# Faceh.net
KiCad netlist of a schematic drawn in EAGLE
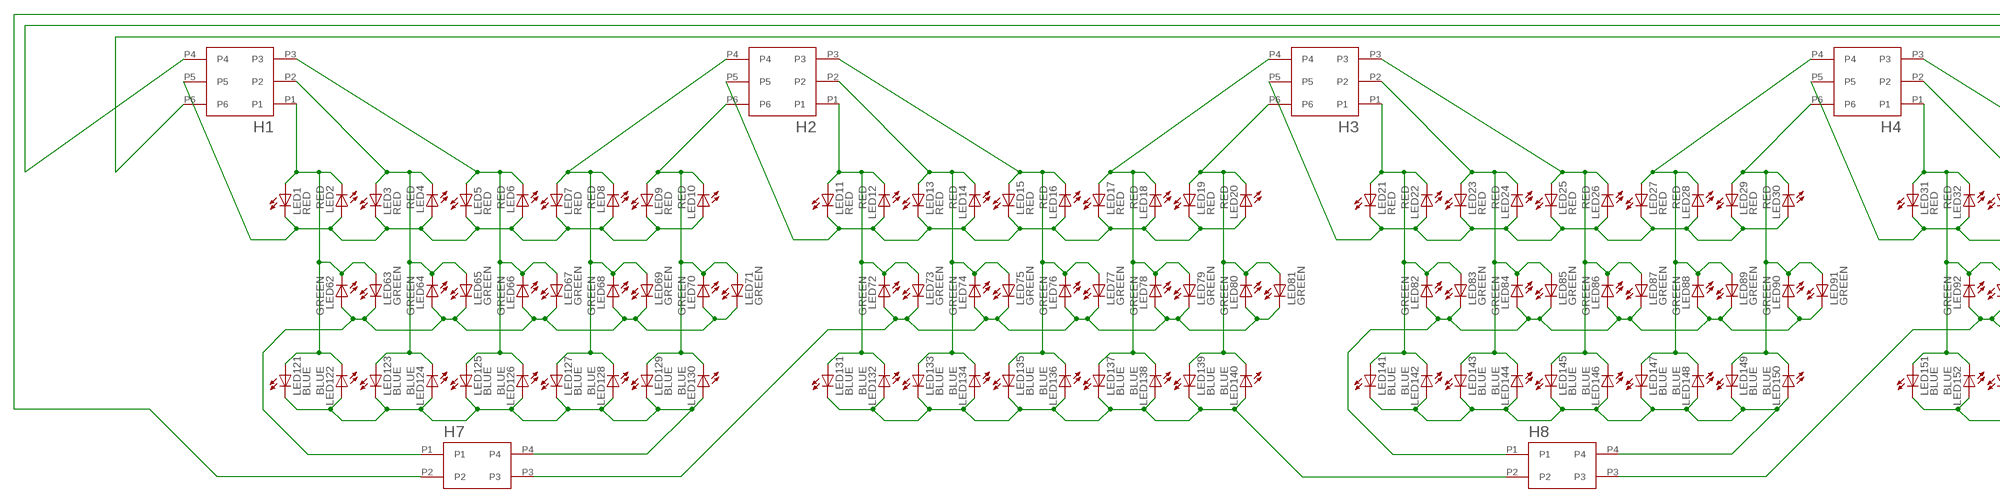
[diagram p0: schematic, sheet 1, part 1 of 2]
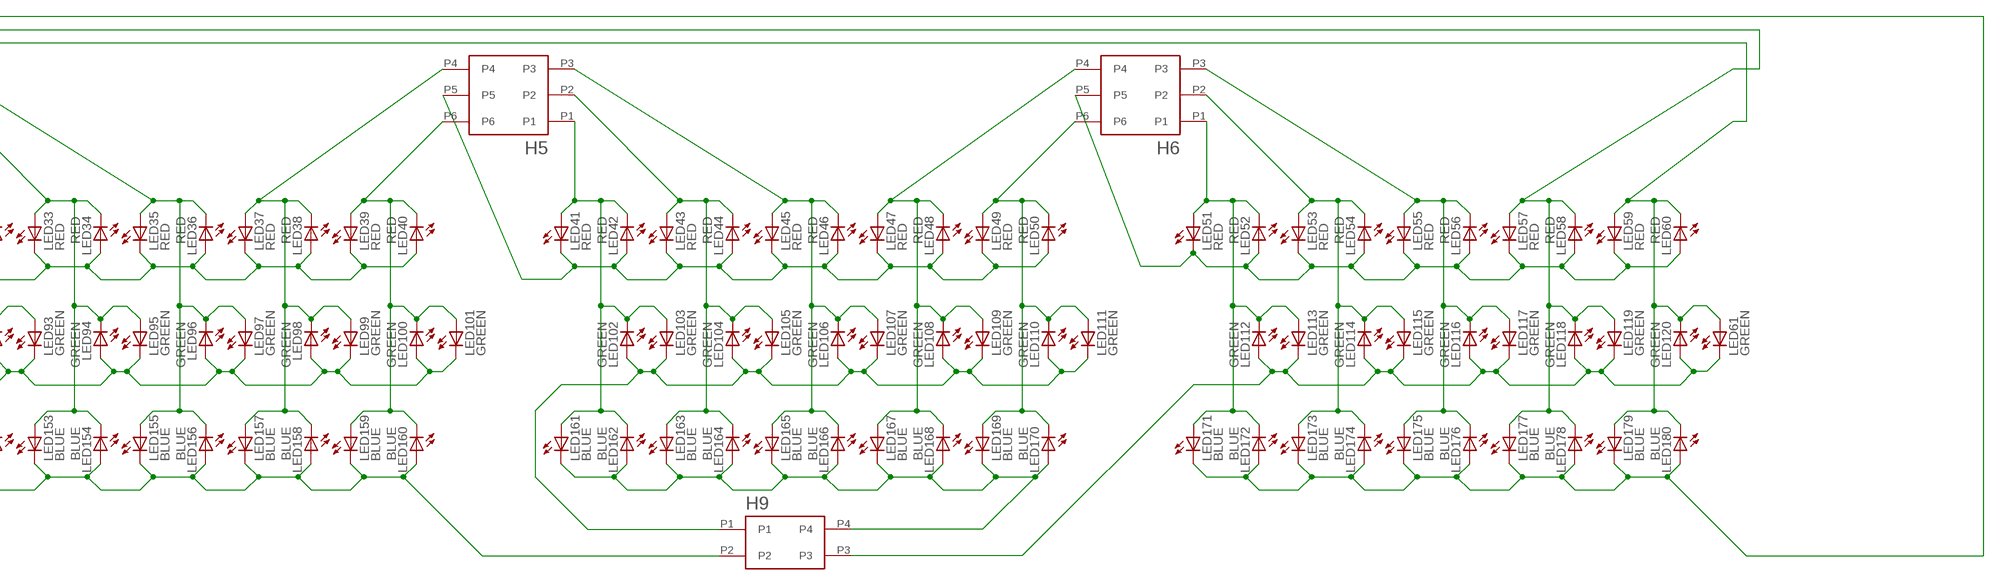
[diagram p1: schematic, sheet 1, part 2 of 2]

(export (version "E")
  (design (tool "Eeschema 10.0.6"))
  (components
    (comp (ref "H1")
      (value "2X3")
      (footprint "eagle-import:3X2_1MM_SMD")
      (libsource (lib "eagle-import") (part "2X3"))
    )
    (comp (ref "H2")
      (value "2X3")
      (footprint "eagle-import:3X2_1MM_SMD")
      (libsource (lib "eagle-import") (part "2X3"))
    )
    (comp (ref "H3")
      (value "2X3")
      (footprint "eagle-import:3X2_1MM_SMD")
      (libsource (lib "eagle-import") (part "2X3"))
    )
    (comp (ref "H4")
      (value "2X3")
      (footprint "eagle-import:3X2_1MM_SMD")
      (libsource (lib "eagle-import") (part "2X3"))
    )
    (comp (ref "H5")
      (value "2X3")
      (footprint "eagle-import:3X2_1MM_SMD")
      (libsource (lib "eagle-import") (part "2X3"))
    )
    (comp (ref "H6")
      (value "2X3")
      (footprint "eagle-import:3X2_1MM_SMD")
      (libsource (lib "eagle-import") (part "2X3"))
    )
    (comp (ref "H7")
      (value "2X2")
      (footprint "eagle-import:2X2_1MM_SMD")
      (libsource (lib "eagle-import") (part "2X2"))
    )
    (comp (ref "H8")
      (value "2X2")
      (footprint "eagle-import:2X2_1MM_SMD")
      (libsource (lib "eagle-import") (part "2X2"))
    )
    (comp (ref "H9")
      (value "2X2")
      (footprint "eagle-import:2X2_1MM_SMD")
      (libsource (lib "eagle-import") (part "2X2"))
    )
    (comp (ref "LED1")
      (value "RED")
      (footprint "eagle-import:LED-0603")
      (libsource (lib "eagle-import") (part "LED0603"))
    )
    (comp (ref "LED2")
      (value "RED")
      (footprint "eagle-import:LED-0603")
      (libsource (lib "eagle-import") (part "LED0603"))
    )
    (comp (ref "LED3")
      (value "RED")
      (footprint "eagle-import:LED-0603")
      (libsource (lib "eagle-import") (part "LED0603"))
    )
    (comp (ref "LED4")
      (value "RED")
      (footprint "eagle-import:LED-0603")
      (libsource (lib "eagle-import") (part "LED0603"))
    )
    (comp (ref "LED5")
      (value "RED")
      (footprint "eagle-import:LED-0603")
      (libsource (lib "eagle-import") (part "LED0603"))
    )
    (comp (ref "LED6")
      (value "RED")
      (footprint "eagle-import:LED-0603")
      (libsource (lib "eagle-import") (part "LED0603"))
    )
    (comp (ref "LED7")
      (value "RED")
      (footprint "eagle-import:LED-0603")
      (libsource (lib "eagle-import") (part "LED0603"))
    )
    (comp (ref "LED8")
      (value "RED")
      (footprint "eagle-import:LED-0603")
      (libsource (lib "eagle-import") (part "LED0603"))
    )
    (comp (ref "LED9")
      (value "RED")
      (footprint "eagle-import:LED-0603")
      (libsource (lib "eagle-import") (part "LED0603"))
    )
    (comp (ref "LED10")
      (value "RED")
      (footprint "eagle-import:LED-0603")
      (libsource (lib "eagle-import") (part "LED0603"))
    )
    (comp (ref "LED11")
      (value "RED")
      (footprint "eagle-import:LED-0603")
      (libsource (lib "eagle-import") (part "LED0603"))
    )
    (comp (ref "LED12")
      (value "RED")
      (footprint "eagle-import:LED-0603")
      (libsource (lib "eagle-import") (part "LED0603"))
    )
    (comp (ref "LED13")
      (value "RED")
      (footprint "eagle-import:LED-0603")
      (libsource (lib "eagle-import") (part "LED0603"))
    )
    (comp (ref "LED14")
      (value "RED")
      (footprint "eagle-import:LED-0603")
      (libsource (lib "eagle-import") (part "LED0603"))
    )
    (comp (ref "LED15")
      (value "RED")
      (footprint "eagle-import:LED-0603")
      (libsource (lib "eagle-import") (part "LED0603"))
    )
    (comp (ref "LED16")
      (value "RED")
      (footprint "eagle-import:LED-0603")
      (libsource (lib "eagle-import") (part "LED0603"))
    )
    (comp (ref "LED17")
      (value "RED")
      (footprint "eagle-import:LED-0603")
      (libsource (lib "eagle-import") (part "LED0603"))
    )
    (comp (ref "LED18")
      (value "RED")
      (footprint "eagle-import:LED-0603")
      (libsource (lib "eagle-import") (part "LED0603"))
    )
    (comp (ref "LED19")
      (value "RED")
      (footprint "eagle-import:LED-0603")
      (libsource (lib "eagle-import") (part "LED0603"))
    )
    (comp (ref "LED20")
      (value "RED")
      (footprint "eagle-import:LED-0603")
      (libsource (lib "eagle-import") (part "LED0603"))
    )
    (comp (ref "LED21")
      (value "RED")
      (footprint "eagle-import:LED-0603")
      (libsource (lib "eagle-import") (part "LED0603"))
    )
    (comp (ref "LED22")
      (value "RED")
      (footprint "eagle-import:LED-0603")
      (libsource (lib "eagle-import") (part "LED0603"))
    )
    (comp (ref "LED23")
      (value "RED")
      (footprint "eagle-import:LED-0603")
      (libsource (lib "eagle-import") (part "LED0603"))
    )
    (comp (ref "LED24")
      (value "RED")
      (footprint "eagle-import:LED-0603")
      (libsource (lib "eagle-import") (part "LED0603"))
    )
    (comp (ref "LED25")
      (value "RED")
      (footprint "eagle-import:LED-0603")
      (libsource (lib "eagle-import") (part "LED0603"))
    )
    (comp (ref "LED26")
      (value "RED")
      (footprint "eagle-import:LED-0603")
      (libsource (lib "eagle-import") (part "LED0603"))
    )
    (comp (ref "LED27")
      (value "RED")
      (footprint "eagle-import:LED-0603")
      (libsource (lib "eagle-import") (part "LED0603"))
    )
    (comp (ref "LED28")
      (value "RED")
      (footprint "eagle-import:LED-0603")
      (libsource (lib "eagle-import") (part "LED0603"))
    )
    (comp (ref "LED29")
      (value "RED")
      (footprint "eagle-import:LED-0603")
      (libsource (lib "eagle-import") (part "LED0603"))
    )
    (comp (ref "LED30")
      (value "RED")
      (footprint "eagle-import:LED-0603")
      (libsource (lib "eagle-import") (part "LED0603"))
    )
    (comp (ref "LED31")
      (value "RED")
      (footprint "eagle-import:LED-0603")
      (libsource (lib "eagle-import") (part "LED0603"))
    )
    (comp (ref "LED32")
      (value "RED")
      (footprint "eagle-import:LED-0603")
      (libsource (lib "eagle-import") (part "LED0603"))
    )
    (comp (ref "LED33")
      (value "RED")
      (footprint "eagle-import:LED-0603")
      (libsource (lib "eagle-import") (part "LED0603"))
    )
    (comp (ref "LED34")
      (value "RED")
      (footprint "eagle-import:LED-0603")
      (libsource (lib "eagle-import") (part "LED0603"))
    )
    (comp (ref "LED35")
      (value "RED")
      (footprint "eagle-import:LED-0603")
      (libsource (lib "eagle-import") (part "LED0603"))
    )
    (comp (ref "LED36")
      (value "RED")
      (footprint "eagle-import:LED-0603")
      (libsource (lib "eagle-import") (part "LED0603"))
    )
    (comp (ref "LED37")
      (value "RED")
      (footprint "eagle-import:LED-0603")
      (libsource (lib "eagle-import") (part "LED0603"))
    )
    (comp (ref "LED38")
      (value "RED")
      (footprint "eagle-import:LED-0603")
      (libsource (lib "eagle-import") (part "LED0603"))
    )
    (comp (ref "LED39")
      (value "RED")
      (footprint "eagle-import:LED-0603")
      (libsource (lib "eagle-import") (part "LED0603"))
    )
    (comp (ref "LED40")
      (value "RED")
      (footprint "eagle-import:LED-0603")
      (libsource (lib "eagle-import") (part "LED0603"))
    )
    (comp (ref "LED41")
      (value "RED")
      (footprint "eagle-import:LED-0603")
      (libsource (lib "eagle-import") (part "LED0603"))
    )
    (comp (ref "LED42")
      (value "RED")
      (footprint "eagle-import:LED-0603")
      (libsource (lib "eagle-import") (part "LED0603"))
    )
    (comp (ref "LED43")
      (value "RED")
      (footprint "eagle-import:LED-0603")
      (libsource (lib "eagle-import") (part "LED0603"))
    )
    (comp (ref "LED44")
      (value "RED")
      (footprint "eagle-import:LED-0603")
      (libsource (lib "eagle-import") (part "LED0603"))
    )
    (comp (ref "LED45")
      (value "RED")
      (footprint "eagle-import:LED-0603")
      (libsource (lib "eagle-import") (part "LED0603"))
    )
    (comp (ref "LED46")
      (value "RED")
      (footprint "eagle-import:LED-0603")
      (libsource (lib "eagle-import") (part "LED0603"))
    )
    (comp (ref "LED47")
      (value "RED")
      (footprint "eagle-import:LED-0603")
      (libsource (lib "eagle-import") (part "LED0603"))
    )
    (comp (ref "LED48")
      (value "RED")
      (footprint "eagle-import:LED-0603")
      (libsource (lib "eagle-import") (part "LED0603"))
    )
    (comp (ref "LED49")
      (value "RED")
      (footprint "eagle-import:LED-0603")
      (libsource (lib "eagle-import") (part "LED0603"))
    )
    (comp (ref "LED50")
      (value "RED")
      (footprint "eagle-import:LED-0603")
      (libsource (lib "eagle-import") (part "LED0603"))
    )
    (comp (ref "LED51")
      (value "RED")
      (footprint "eagle-import:LED-0603")
      (libsource (lib "eagle-import") (part "LED0603"))
    )
    (comp (ref "LED52")
      (value "RED")
      (footprint "eagle-import:LED-0603")
      (libsource (lib "eagle-import") (part "LED0603"))
    )
    (comp (ref "LED53")
      (value "RED")
      (footprint "eagle-import:LED-0603")
      (libsource (lib "eagle-import") (part "LED0603"))
    )
    (comp (ref "LED54")
      (value "RED")
      (footprint "eagle-import:LED-0603")
      (libsource (lib "eagle-import") (part "LED0603"))
    )
    (comp (ref "LED55")
      (value "RED")
      (footprint "eagle-import:LED-0603")
      (libsource (lib "eagle-import") (part "LED0603"))
    )
    (comp (ref "LED56")
      (value "RED")
      (footprint "eagle-import:LED-0603")
      (libsource (lib "eagle-import") (part "LED0603"))
    )
    (comp (ref "LED57")
      (value "RED")
      (footprint "eagle-import:LED-0603")
      (libsource (lib "eagle-import") (part "LED0603"))
    )
    (comp (ref "LED58")
      (value "RED")
      (footprint "eagle-import:LED-0603")
      (libsource (lib "eagle-import") (part "LED0603"))
    )
    (comp (ref "LED59")
      (value "RED")
      (footprint "eagle-import:LED-0603")
      (libsource (lib "eagle-import") (part "LED0603"))
    )
    (comp (ref "LED60")
      (value "RED")
      (footprint "eagle-import:LED-0603")
      (libsource (lib "eagle-import") (part "LED0603"))
    )
    (comp (ref "LED61")
      (value "GREEN")
      (footprint "eagle-import:LED-0603")
      (libsource (lib "eagle-import") (part "LED0603"))
    )
    (comp (ref "LED62")
      (value "GREEN")
      (footprint "eagle-import:LED-0603")
      (libsource (lib "eagle-import") (part "LED0603"))
    )
    (comp (ref "LED63")
      (value "GREEN")
      (footprint "eagle-import:LED-0603")
      (libsource (lib "eagle-import") (part "LED0603"))
    )
    (comp (ref "LED64")
      (value "GREEN")
      (footprint "eagle-import:LED-0603")
      (libsource (lib "eagle-import") (part "LED0603"))
    )
    (comp (ref "LED65")
      (value "GREEN")
      (footprint "eagle-import:LED-0603")
      (libsource (lib "eagle-import") (part "LED0603"))
    )
    (comp (ref "LED66")
      (value "GREEN")
      (footprint "eagle-import:LED-0603")
      (libsource (lib "eagle-import") (part "LED0603"))
    )
    (comp (ref "LED67")
      (value "GREEN")
      (footprint "eagle-import:LED-0603")
      (libsource (lib "eagle-import") (part "LED0603"))
    )
    (comp (ref "LED68")
      (value "GREEN")
      (footprint "eagle-import:LED-0603")
      (libsource (lib "eagle-import") (part "LED0603"))
    )
    (comp (ref "LED69")
      (value "GREEN")
      (footprint "eagle-import:LED-0603")
      (libsource (lib "eagle-import") (part "LED0603"))
    )
    (comp (ref "LED70")
      (value "GREEN")
      (footprint "eagle-import:LED-0603")
      (libsource (lib "eagle-import") (part "LED0603"))
    )
    (comp (ref "LED71")
      (value "GREEN")
      (footprint "eagle-import:LED-0603")
      (libsource (lib "eagle-import") (part "LED0603"))
    )
    (comp (ref "LED72")
      (value "GREEN")
      (footprint "eagle-import:LED-0603")
      (libsource (lib "eagle-import") (part "LED0603"))
    )
    (comp (ref "LED73")
      (value "GREEN")
      (footprint "eagle-import:LED-0603")
      (libsource (lib "eagle-import") (part "LED0603"))
    )
    (comp (ref "LED74")
      (value "GREEN")
      (footprint "eagle-import:LED-0603")
      (libsource (lib "eagle-import") (part "LED0603"))
    )
    (comp (ref "LED75")
      (value "GREEN")
      (footprint "eagle-import:LED-0603")
      (libsource (lib "eagle-import") (part "LED0603"))
    )
    (comp (ref "LED76")
      (value "GREEN")
      (footprint "eagle-import:LED-0603")
      (libsource (lib "eagle-import") (part "LED0603"))
    )
    (comp (ref "LED77")
      (value "GREEN")
      (footprint "eagle-import:LED-0603")
      (libsource (lib "eagle-import") (part "LED0603"))
    )
    (comp (ref "LED78")
      (value "GREEN")
      (footprint "eagle-import:LED-0603")
      (libsource (lib "eagle-import") (part "LED0603"))
    )
    (comp (ref "LED79")
      (value "GREEN")
      (footprint "eagle-import:LED-0603")
      (libsource (lib "eagle-import") (part "LED0603"))
    )
    (comp (ref "LED80")
      (value "GREEN")
      (footprint "eagle-import:LED-0603")
      (libsource (lib "eagle-import") (part "LED0603"))
    )
    (comp (ref "LED81")
      (value "GREEN")
      (footprint "eagle-import:LED-0603")
      (libsource (lib "eagle-import") (part "LED0603"))
    )
    (comp (ref "LED82")
      (value "GREEN")
      (footprint "eagle-import:LED-0603")
      (libsource (lib "eagle-import") (part "LED0603"))
    )
    (comp (ref "LED83")
      (value "GREEN")
      (footprint "eagle-import:LED-0603")
      (libsource (lib "eagle-import") (part "LED0603"))
    )
    (comp (ref "LED84")
      (value "GREEN")
      (footprint "eagle-import:LED-0603")
      (libsource (lib "eagle-import") (part "LED0603"))
    )
    (comp (ref "LED85")
      (value "GREEN")
      (footprint "eagle-import:LED-0603")
      (libsource (lib "eagle-import") (part "LED0603"))
    )
    (comp (ref "LED86")
      (value "GREEN")
      (footprint "eagle-import:LED-0603")
      (libsource (lib "eagle-import") (part "LED0603"))
    )
    (comp (ref "LED87")
      (value "GREEN")
      (footprint "eagle-import:LED-0603")
      (libsource (lib "eagle-import") (part "LED0603"))
    )
    (comp (ref "LED88")
      (value "GREEN")
      (footprint "eagle-import:LED-0603")
      (libsource (lib "eagle-import") (part "LED0603"))
    )
    (comp (ref "LED89")
      (value "GREEN")
      (footprint "eagle-import:LED-0603")
      (libsource (lib "eagle-import") (part "LED0603"))
    )
    (comp (ref "LED90")
      (value "GREEN")
      (footprint "eagle-import:LED-0603")
      (libsource (lib "eagle-import") (part "LED0603"))
    )
    (comp (ref "LED91")
      (value "GREEN")
      (footprint "eagle-import:LED-0603")
      (libsource (lib "eagle-import") (part "LED0603"))
    )
    (comp (ref "LED92")
      (value "GREEN")
      (footprint "eagle-import:LED-0603")
      (libsource (lib "eagle-import") (part "LED0603"))
    )
    (comp (ref "LED93")
      (value "GREEN")
      (footprint "eagle-import:LED-0603")
      (libsource (lib "eagle-import") (part "LED0603"))
    )
    (comp (ref "LED94")
      (value "GREEN")
      (footprint "eagle-import:LED-0603")
      (libsource (lib "eagle-import") (part "LED0603"))
    )
    (comp (ref "LED95")
      (value "GREEN")
      (footprint "eagle-import:LED-0603")
      (libsource (lib "eagle-import") (part "LED0603"))
    )
    (comp (ref "LED96")
      (value "GREEN")
      (footprint "eagle-import:LED-0603")
      (libsource (lib "eagle-import") (part "LED0603"))
    )
    (comp (ref "LED97")
      (value "GREEN")
      (footprint "eagle-import:LED-0603")
      (libsource (lib "eagle-import") (part "LED0603"))
    )
    (comp (ref "LED98")
      (value "GREEN")
      (footprint "eagle-import:LED-0603")
      (libsource (lib "eagle-import") (part "LED0603"))
    )
    (comp (ref "LED99")
      (value "GREEN")
      (footprint "eagle-import:LED-0603")
      (libsource (lib "eagle-import") (part "LED0603"))
    )
    (comp (ref "LED100")
      (value "GREEN")
      (footprint "eagle-import:LED-0603")
      (libsource (lib "eagle-import") (part "LED0603"))
    )
    (comp (ref "LED101")
      (value "GREEN")
      (footprint "eagle-import:LED-0603")
      (libsource (lib "eagle-import") (part "LED0603"))
    )
    (comp (ref "LED102")
      (value "GREEN")
      (footprint "eagle-import:LED-0603")
      (libsource (lib "eagle-import") (part "LED0603"))
    )
    (comp (ref "LED103")
      (value "GREEN")
      (footprint "eagle-import:LED-0603")
      (libsource (lib "eagle-import") (part "LED0603"))
    )
    (comp (ref "LED104")
      (value "GREEN")
      (footprint "eagle-import:LED-0603")
      (libsource (lib "eagle-import") (part "LED0603"))
    )
    (comp (ref "LED105")
      (value "GREEN")
      (footprint "eagle-import:LED-0603")
      (libsource (lib "eagle-import") (part "LED0603"))
    )
    (comp (ref "LED106")
      (value "GREEN")
      (footprint "eagle-import:LED-0603")
      (libsource (lib "eagle-import") (part "LED0603"))
    )
    (comp (ref "LED107")
      (value "GREEN")
      (footprint "eagle-import:LED-0603")
      (libsource (lib "eagle-import") (part "LED0603"))
    )
    (comp (ref "LED108")
      (value "GREEN")
      (footprint "eagle-import:LED-0603")
      (libsource (lib "eagle-import") (part "LED0603"))
    )
    (comp (ref "LED109")
      (value "GREEN")
      (footprint "eagle-import:LED-0603")
      (libsource (lib "eagle-import") (part "LED0603"))
    )
    (comp (ref "LED110")
      (value "GREEN")
      (footprint "eagle-import:LED-0603")
      (libsource (lib "eagle-import") (part "LED0603"))
    )
    (comp (ref "LED111")
      (value "GREEN")
      (footprint "eagle-import:LED-0603")
      (libsource (lib "eagle-import") (part "LED0603"))
    )
    (comp (ref "LED112")
      (value "GREEN")
      (footprint "eagle-import:LED-0603")
      (libsource (lib "eagle-import") (part "LED0603"))
    )
    (comp (ref "LED113")
      (value "GREEN")
      (footprint "eagle-import:LED-0603")
      (libsource (lib "eagle-import") (part "LED0603"))
    )
    (comp (ref "LED114")
      (value "GREEN")
      (footprint "eagle-import:LED-0603")
      (libsource (lib "eagle-import") (part "LED0603"))
    )
    (comp (ref "LED115")
      (value "GREEN")
      (footprint "eagle-import:LED-0603")
      (libsource (lib "eagle-import") (part "LED0603"))
    )
    (comp (ref "LED116")
      (value "GREEN")
      (footprint "eagle-import:LED-0603")
      (libsource (lib "eagle-import") (part "LED0603"))
    )
    (comp (ref "LED117")
      (value "GREEN")
      (footprint "eagle-import:LED-0603")
      (libsource (lib "eagle-import") (part "LED0603"))
    )
    (comp (ref "LED118")
      (value "GREEN")
      (footprint "eagle-import:LED-0603")
      (libsource (lib "eagle-import") (part "LED0603"))
    )
    (comp (ref "LED119")
      (value "GREEN")
      (footprint "eagle-import:LED-0603")
      (libsource (lib "eagle-import") (part "LED0603"))
    )
    (comp (ref "LED120")
      (value "GREEN")
      (footprint "eagle-import:LED-0603")
      (libsource (lib "eagle-import") (part "LED0603"))
    )
    (comp (ref "LED121")
      (value "BLUE")
      (footprint "eagle-import:LED-0603")
      (libsource (lib "eagle-import") (part "LED0603"))
    )
    (comp (ref "LED122")
      (value "BLUE")
      (footprint "eagle-import:LED-0603")
      (libsource (lib "eagle-import") (part "LED0603"))
    )
    (comp (ref "LED123")
      (value "BLUE")
      (footprint "eagle-import:LED-0603")
      (libsource (lib "eagle-import") (part "LED0603"))
    )
    (comp (ref "LED124")
      (value "BLUE")
      (footprint "eagle-import:LED-0603")
      (libsource (lib "eagle-import") (part "LED0603"))
    )
    (comp (ref "LED125")
      (value "BLUE")
      (footprint "eagle-import:LED-0603")
      (libsource (lib "eagle-import") (part "LED0603"))
    )
    (comp (ref "LED126")
      (value "BLUE")
      (footprint "eagle-import:LED-0603")
      (libsource (lib "eagle-import") (part "LED0603"))
    )
    (comp (ref "LED127")
      (value "BLUE")
      (footprint "eagle-import:LED-0603")
      (libsource (lib "eagle-import") (part "LED0603"))
    )
    (comp (ref "LED128")
      (value "BLUE")
      (footprint "eagle-import:LED-0603")
      (libsource (lib "eagle-import") (part "LED0603"))
    )
    (comp (ref "LED129")
      (value "BLUE")
      (footprint "eagle-import:LED-0603")
      (libsource (lib "eagle-import") (part "LED0603"))
    )
    (comp (ref "LED130")
      (value "BLUE")
      (footprint "eagle-import:LED-0603")
      (libsource (lib "eagle-import") (part "LED0603"))
    )
    (comp (ref "LED131")
      (value "BLUE")
      (footprint "eagle-import:LED-0603")
      (libsource (lib "eagle-import") (part "LED0603"))
    )
    (comp (ref "LED132")
      (value "BLUE")
      (footprint "eagle-import:LED-0603")
      (libsource (lib "eagle-import") (part "LED0603"))
    )
    (comp (ref "LED133")
      (value "BLUE")
      (footprint "eagle-import:LED-0603")
      (libsource (lib "eagle-import") (part "LED0603"))
    )
    (comp (ref "LED134")
      (value "BLUE")
      (footprint "eagle-import:LED-0603")
      (libsource (lib "eagle-import") (part "LED0603"))
    )
    (comp (ref "LED135")
      (value "BLUE")
      (footprint "eagle-import:LED-0603")
      (libsource (lib "eagle-import") (part "LED0603"))
    )
    (comp (ref "LED136")
      (value "BLUE")
      (footprint "eagle-import:LED-0603")
      (libsource (lib "eagle-import") (part "LED0603"))
    )
    (comp (ref "LED137")
      (value "BLUE")
      (footprint "eagle-import:LED-0603")
      (libsource (lib "eagle-import") (part "LED0603"))
    )
    (comp (ref "LED138")
      (value "BLUE")
      (footprint "eagle-import:LED-0603")
      (libsource (lib "eagle-import") (part "LED0603"))
    )
    (comp (ref "LED139")
      (value "BLUE")
      (footprint "eagle-import:LED-0603")
      (libsource (lib "eagle-import") (part "LED0603"))
    )
    (comp (ref "LED140")
      (value "BLUE")
      (footprint "eagle-import:LED-0603")
      (libsource (lib "eagle-import") (part "LED0603"))
    )
    (comp (ref "LED141")
      (value "BLUE")
      (footprint "eagle-import:LED-0603")
      (libsource (lib "eagle-import") (part "LED0603"))
    )
    (comp (ref "LED142")
      (value "BLUE")
      (footprint "eagle-import:LED-0603")
      (libsource (lib "eagle-import") (part "LED0603"))
    )
    (comp (ref "LED143")
      (value "BLUE")
      (footprint "eagle-import:LED-0603")
      (libsource (lib "eagle-import") (part "LED0603"))
    )
    (comp (ref "LED144")
      (value "BLUE")
      (footprint "eagle-import:LED-0603")
      (libsource (lib "eagle-import") (part "LED0603"))
    )
    (comp (ref "LED145")
      (value "BLUE")
      (footprint "eagle-import:LED-0603")
      (libsource (lib "eagle-import") (part "LED0603"))
    )
    (comp (ref "LED146")
      (value "BLUE")
      (footprint "eagle-import:LED-0603")
      (libsource (lib "eagle-import") (part "LED0603"))
    )
    (comp (ref "LED147")
      (value "BLUE")
      (footprint "eagle-import:LED-0603")
      (libsource (lib "eagle-import") (part "LED0603"))
    )
    (comp (ref "LED148")
      (value "BLUE")
      (footprint "eagle-import:LED-0603")
      (libsource (lib "eagle-import") (part "LED0603"))
    )
    (comp (ref "LED149")
      (value "BLUE")
      (footprint "eagle-import:LED-0603")
      (libsource (lib "eagle-import") (part "LED0603"))
    )
    (comp (ref "LED150")
      (value "BLUE")
      (footprint "eagle-import:LED-0603")
      (libsource (lib "eagle-import") (part "LED0603"))
    )
    (comp (ref "LED151")
      (value "BLUE")
      (footprint "eagle-import:LED-0603")
      (libsource (lib "eagle-import") (part "LED0603"))
    )
    (comp (ref "LED152")
      (value "BLUE")
      (footprint "eagle-import:LED-0603")
      (libsource (lib "eagle-import") (part "LED0603"))
    )
    (comp (ref "LED153")
      (value "BLUE")
      (footprint "eagle-import:LED-0603")
      (libsource (lib "eagle-import") (part "LED0603"))
    )
    (comp (ref "LED154")
      (value "BLUE")
      (footprint "eagle-import:LED-0603")
      (libsource (lib "eagle-import") (part "LED0603"))
    )
    (comp (ref "LED155")
      (value "BLUE")
      (footprint "eagle-import:LED-0603")
      (libsource (lib "eagle-import") (part "LED0603"))
    )
    (comp (ref "LED156")
      (value "BLUE")
      (footprint "eagle-import:LED-0603")
      (libsource (lib "eagle-import") (part "LED0603"))
    )
    (comp (ref "LED157")
      (value "BLUE")
      (footprint "eagle-import:LED-0603")
      (libsource (lib "eagle-import") (part "LED0603"))
    )
    (comp (ref "LED158")
      (value "BLUE")
      (footprint "eagle-import:LED-0603")
      (libsource (lib "eagle-import") (part "LED0603"))
    )
    (comp (ref "LED159")
      (value "BLUE")
      (footprint "eagle-import:LED-0603")
      (libsource (lib "eagle-import") (part "LED0603"))
    )
    (comp (ref "LED160")
      (value "BLUE")
      (footprint "eagle-import:LED-0603")
      (libsource (lib "eagle-import") (part "LED0603"))
    )
    (comp (ref "LED161")
      (value "BLUE")
      (footprint "eagle-import:LED-0603")
      (libsource (lib "eagle-import") (part "LED0603"))
    )
    (comp (ref "LED162")
      (value "BLUE")
      (footprint "eagle-import:LED-0603")
      (libsource (lib "eagle-import") (part "LED0603"))
    )
    (comp (ref "LED163")
      (value "BLUE")
      (footprint "eagle-import:LED-0603")
      (libsource (lib "eagle-import") (part "LED0603"))
    )
    (comp (ref "LED164")
      (value "BLUE")
      (footprint "eagle-import:LED-0603")
      (libsource (lib "eagle-import") (part "LED0603"))
    )
    (comp (ref "LED165")
      (value "BLUE")
      (footprint "eagle-import:LED-0603")
      (libsource (lib "eagle-import") (part "LED0603"))
    )
    (comp (ref "LED166")
      (value "BLUE")
      (footprint "eagle-import:LED-0603")
      (libsource (lib "eagle-import") (part "LED0603"))
    )
    (comp (ref "LED167")
      (value "BLUE")
      (footprint "eagle-import:LED-0603")
      (libsource (lib "eagle-import") (part "LED0603"))
    )
    (comp (ref "LED168")
      (value "BLUE")
      (footprint "eagle-import:LED-0603")
      (libsource (lib "eagle-import") (part "LED0603"))
    )
    (comp (ref "LED169")
      (value "BLUE")
      (footprint "eagle-import:LED-0603")
      (libsource (lib "eagle-import") (part "LED0603"))
    )
    (comp (ref "LED170")
      (value "BLUE")
      (footprint "eagle-import:LED-0603")
      (libsource (lib "eagle-import") (part "LED0603"))
    )
    (comp (ref "LED171")
      (value "BLUE")
      (footprint "eagle-import:LED-0603")
      (libsource (lib "eagle-import") (part "LED0603"))
    )
    (comp (ref "LED172")
      (value "BLUE")
      (footprint "eagle-import:LED-0603")
      (libsource (lib "eagle-import") (part "LED0603"))
    )
    (comp (ref "LED173")
      (value "BLUE")
      (footprint "eagle-import:LED-0603")
      (libsource (lib "eagle-import") (part "LED0603"))
    )
    (comp (ref "LED174")
      (value "BLUE")
      (footprint "eagle-import:LED-0603")
      (libsource (lib "eagle-import") (part "LED0603"))
    )
    (comp (ref "LED175")
      (value "BLUE")
      (footprint "eagle-import:LED-0603")
      (libsource (lib "eagle-import") (part "LED0603"))
    )
    (comp (ref "LED176")
      (value "BLUE")
      (footprint "eagle-import:LED-0603")
      (libsource (lib "eagle-import") (part "LED0603"))
    )
    (comp (ref "LED177")
      (value "BLUE")
      (footprint "eagle-import:LED-0603")
      (libsource (lib "eagle-import") (part "LED0603"))
    )
    (comp (ref "LED178")
      (value "BLUE")
      (footprint "eagle-import:LED-0603")
      (libsource (lib "eagle-import") (part "LED0603"))
    )
    (comp (ref "LED179")
      (value "BLUE")
      (footprint "eagle-import:LED-0603")
      (libsource (lib "eagle-import") (part "LED0603"))
    )
    (comp (ref "LED180")
      (value "BLUE")
      (footprint "eagle-import:LED-0603")
      (libsource (lib "eagle-import") (part "LED0603"))
    )
  )
  (nets
    (net (code "1") (name "Net-(H1-PadP1)") (class "Default")
      (node (ref "H1") (pin "P1") (pinfunction "P1_P1") (pintype "bidirectional"))
      (node (ref "LED1") (pin "A") (pinfunction "A_A") (pintype "passive"))
      (node (ref "LED121") (pin "A") (pinfunction "A_A") (pintype "passive"))
      (node (ref "LED122") (pin "C") (pinfunction "C_C") (pintype "passive"))
      (node (ref "LED2") (pin "C") (pinfunction "C_C") (pintype "passive"))
      (node (ref "LED62") (pin "C") (pinfunction "C_C") (pintype "passive"))
      (node (ref "LED63") (pin "A") (pinfunction "A_A") (pintype "passive"))
    )
    (net (code "2") (name "Net-(H1-PadP2)") (class "Default")
      (node (ref "H1") (pin "P2") (pinfunction "P2_P2") (pintype "bidirectional"))
      (node (ref "LED123") (pin "A") (pinfunction "A_A") (pintype "passive"))
      (node (ref "LED124") (pin "C") (pinfunction "C_C") (pintype "passive"))
      (node (ref "LED3") (pin "A") (pinfunction "A_A") (pintype "passive"))
      (node (ref "LED4") (pin "C") (pinfunction "C_C") (pintype "passive"))
      (node (ref "LED64") (pin "C") (pinfunction "C_C") (pintype "passive"))
      (node (ref "LED65") (pin "A") (pinfunction "A_A") (pintype "passive"))
    )
    (net (code "3") (name "Net-(H1-PadP3)") (class "Default")
      (node (ref "H1") (pin "P3") (pinfunction "P3_P3") (pintype "bidirectional"))
      (node (ref "LED125") (pin "A") (pinfunction "A_A") (pintype "passive"))
      (node (ref "LED126") (pin "C") (pinfunction "C_C") (pintype "passive"))
      (node (ref "LED5") (pin "A") (pinfunction "A_A") (pintype "passive"))
      (node (ref "LED6") (pin "C") (pinfunction "C_C") (pintype "passive"))
      (node (ref "LED66") (pin "C") (pinfunction "C_C") (pintype "passive"))
      (node (ref "LED67") (pin "A") (pinfunction "A_A") (pintype "passive"))
    )
    (net (code "4") (name "Net-(H1-PadP4)") (class "Default")
      (node (ref "H1") (pin "P4") (pinfunction "P4_P4") (pintype "bidirectional"))
      (node (ref "LED118") (pin "C") (pinfunction "C_C") (pintype "passive"))
      (node (ref "LED119") (pin "A") (pinfunction "A_A") (pintype "passive"))
      (node (ref "LED177") (pin "A") (pinfunction "A_A") (pintype "passive"))
      (node (ref "LED178") (pin "C") (pinfunction "C_C") (pintype "passive"))
      (node (ref "LED57") (pin "A") (pinfunction "A_A") (pintype "passive"))
      (node (ref "LED58") (pin "C") (pinfunction "C_C") (pintype "passive"))
    )
    (net (code "5") (name "Net-(H1-PadP5)") (class "Default")
      (node (ref "H1") (pin "P5") (pinfunction "P5_P5") (pintype "bidirectional"))
      (node (ref "LED1") (pin "C") (pinfunction "C_C") (pintype "passive"))
      (node (ref "LED10") (pin "A") (pinfunction "A_A") (pintype "passive"))
      (node (ref "LED2") (pin "A") (pinfunction "A_A") (pintype "passive"))
      (node (ref "LED3") (pin "C") (pinfunction "C_C") (pintype "passive"))
      (node (ref "LED4") (pin "A") (pinfunction "A_A") (pintype "passive"))
      (node (ref "LED5") (pin "C") (pinfunction "C_C") (pintype "passive"))
      (node (ref "LED6") (pin "A") (pinfunction "A_A") (pintype "passive"))
      (node (ref "LED7") (pin "C") (pinfunction "C_C") (pintype "passive"))
      (node (ref "LED8") (pin "A") (pinfunction "A_A") (pintype "passive"))
      (node (ref "LED9") (pin "C") (pinfunction "C_C") (pintype "passive"))
    )
    (net (code "6") (name "Net-(H1-PadP6)") (class "Default")
      (node (ref "H1") (pin "P6") (pinfunction "P6_P6") (pintype "bidirectional"))
      (node (ref "LED120") (pin "C") (pinfunction "C_C") (pintype "passive"))
      (node (ref "LED179") (pin "A") (pinfunction "A_A") (pintype "passive"))
      (node (ref "LED180") (pin "C") (pinfunction "C_C") (pintype "passive"))
      (node (ref "LED59") (pin "A") (pinfunction "A_A") (pintype "passive"))
      (node (ref "LED60") (pin "C") (pinfunction "C_C") (pintype "passive"))
      (node (ref "LED61") (pin "A") (pinfunction "A_A") (pintype "passive"))
    )
    (net (code "7") (name "Net-(H2-PadP1)") (class "Default")
      (node (ref "H2") (pin "P1") (pinfunction "P1_P1") (pintype "bidirectional"))
      (node (ref "LED11") (pin "A") (pinfunction "A_A") (pintype "passive"))
      (node (ref "LED12") (pin "C") (pinfunction "C_C") (pintype "passive"))
      (node (ref "LED131") (pin "A") (pinfunction "A_A") (pintype "passive"))
      (node (ref "LED132") (pin "C") (pinfunction "C_C") (pintype "passive"))
      (node (ref "LED72") (pin "C") (pinfunction "C_C") (pintype "passive"))
      (node (ref "LED73") (pin "A") (pinfunction "A_A") (pintype "passive"))
    )
    (net (code "8") (name "Net-(H2-PadP2)") (class "Default")
      (node (ref "H2") (pin "P2") (pinfunction "P2_P2") (pintype "bidirectional"))
      (node (ref "LED13") (pin "A") (pinfunction "A_A") (pintype "passive"))
      (node (ref "LED133") (pin "A") (pinfunction "A_A") (pintype "passive"))
      (node (ref "LED134") (pin "C") (pinfunction "C_C") (pintype "passive"))
      (node (ref "LED14") (pin "C") (pinfunction "C_C") (pintype "passive"))
      (node (ref "LED74") (pin "C") (pinfunction "C_C") (pintype "passive"))
      (node (ref "LED75") (pin "A") (pinfunction "A_A") (pintype "passive"))
    )
    (net (code "9") (name "Net-(H2-PadP3)") (class "Default")
      (node (ref "H2") (pin "P3") (pinfunction "P3_P3") (pintype "bidirectional"))
      (node (ref "LED135") (pin "A") (pinfunction "A_A") (pintype "passive"))
      (node (ref "LED136") (pin "C") (pinfunction "C_C") (pintype "passive"))
      (node (ref "LED15") (pin "A") (pinfunction "A_A") (pintype "passive"))
      (node (ref "LED16") (pin "C") (pinfunction "C_C") (pintype "passive"))
      (node (ref "LED76") (pin "C") (pinfunction "C_C") (pintype "passive"))
      (node (ref "LED77") (pin "A") (pinfunction "A_A") (pintype "passive"))
    )
    (net (code "10") (name "Net-(H2-PadP4)") (class "Default")
      (node (ref "H2") (pin "P4") (pinfunction "P4_P4") (pintype "bidirectional"))
      (node (ref "LED127") (pin "A") (pinfunction "A_A") (pintype "passive"))
      (node (ref "LED128") (pin "C") (pinfunction "C_C") (pintype "passive"))
      (node (ref "LED68") (pin "C") (pinfunction "C_C") (pintype "passive"))
      (node (ref "LED69") (pin "A") (pinfunction "A_A") (pintype "passive"))
      (node (ref "LED7") (pin "A") (pinfunction "A_A") (pintype "passive"))
      (node (ref "LED8") (pin "C") (pinfunction "C_C") (pintype "passive"))
    )
    (net (code "11") (name "Net-(H2-PadP5)") (class "Default")
      (node (ref "H2") (pin "P5") (pinfunction "P5_P5") (pintype "bidirectional"))
      (node (ref "LED11") (pin "C") (pinfunction "C_C") (pintype "passive"))
      (node (ref "LED12") (pin "A") (pinfunction "A_A") (pintype "passive"))
      (node (ref "LED13") (pin "C") (pinfunction "C_C") (pintype "passive"))
      (node (ref "LED14") (pin "A") (pinfunction "A_A") (pintype "passive"))
      (node (ref "LED15") (pin "C") (pinfunction "C_C") (pintype "passive"))
      (node (ref "LED16") (pin "A") (pinfunction "A_A") (pintype "passive"))
      (node (ref "LED17") (pin "C") (pinfunction "C_C") (pintype "passive"))
      (node (ref "LED18") (pin "A") (pinfunction "A_A") (pintype "passive"))
      (node (ref "LED19") (pin "C") (pinfunction "C_C") (pintype "passive"))
      (node (ref "LED20") (pin "A") (pinfunction "A_A") (pintype "passive"))
    )
    (net (code "12") (name "Net-(H2-PadP6)") (class "Default")
      (node (ref "H2") (pin "P6") (pinfunction "P6_P6") (pintype "bidirectional"))
      (node (ref "LED10") (pin "C") (pinfunction "C_C") (pintype "passive"))
      (node (ref "LED129") (pin "A") (pinfunction "A_A") (pintype "passive"))
      (node (ref "LED130") (pin "C") (pinfunction "C_C") (pintype "passive"))
      (node (ref "LED70") (pin "C") (pinfunction "C_C") (pintype "passive"))
      (node (ref "LED71") (pin "A") (pinfunction "A_A") (pintype "passive"))
      (node (ref "LED9") (pin "A") (pinfunction "A_A") (pintype "passive"))
    )
    (net (code "13") (name "Net-(H3-PadP1)") (class "Default")
      (node (ref "H3") (pin "P1") (pinfunction "P1_P1") (pintype "bidirectional"))
      (node (ref "LED141") (pin "A") (pinfunction "A_A") (pintype "passive"))
      (node (ref "LED142") (pin "C") (pinfunction "C_C") (pintype "passive"))
      (node (ref "LED21") (pin "A") (pinfunction "A_A") (pintype "passive"))
      (node (ref "LED22") (pin "C") (pinfunction "C_C") (pintype "passive"))
      (node (ref "LED82") (pin "C") (pinfunction "C_C") (pintype "passive"))
      (node (ref "LED83") (pin "A") (pinfunction "A_A") (pintype "passive"))
    )
    (net (code "14") (name "Net-(H3-PadP2)") (class "Default")
      (node (ref "H3") (pin "P2") (pinfunction "P2_P2") (pintype "bidirectional"))
      (node (ref "LED143") (pin "A") (pinfunction "A_A") (pintype "passive"))
      (node (ref "LED144") (pin "C") (pinfunction "C_C") (pintype "passive"))
      (node (ref "LED23") (pin "A") (pinfunction "A_A") (pintype "passive"))
      (node (ref "LED24") (pin "C") (pinfunction "C_C") (pintype "passive"))
      (node (ref "LED84") (pin "C") (pinfunction "C_C") (pintype "passive"))
      (node (ref "LED85") (pin "A") (pinfunction "A_A") (pintype "passive"))
    )
    (net (code "15") (name "Net-(H3-PadP3)") (class "Default")
      (node (ref "H3") (pin "P3") (pinfunction "P3_P3") (pintype "bidirectional"))
      (node (ref "LED145") (pin "A") (pinfunction "A_A") (pintype "passive"))
      (node (ref "LED146") (pin "C") (pinfunction "C_C") (pintype "passive"))
      (node (ref "LED25") (pin "A") (pinfunction "A_A") (pintype "passive"))
      (node (ref "LED26") (pin "C") (pinfunction "C_C") (pintype "passive"))
      (node (ref "LED86") (pin "C") (pinfunction "C_C") (pintype "passive"))
      (node (ref "LED87") (pin "A") (pinfunction "A_A") (pintype "passive"))
    )
    (net (code "16") (name "Net-(H3-PadP4)") (class "Default")
      (node (ref "H3") (pin "P4") (pinfunction "P4_P4") (pintype "bidirectional"))
      (node (ref "LED137") (pin "A") (pinfunction "A_A") (pintype "passive"))
      (node (ref "LED138") (pin "C") (pinfunction "C_C") (pintype "passive"))
      (node (ref "LED17") (pin "A") (pinfunction "A_A") (pintype "passive"))
      (node (ref "LED18") (pin "C") (pinfunction "C_C") (pintype "passive"))
      (node (ref "LED78") (pin "C") (pinfunction "C_C") (pintype "passive"))
      (node (ref "LED79") (pin "A") (pinfunction "A_A") (pintype "passive"))
    )
    (net (code "17") (name "Net-(H3-PadP5)") (class "Default")
      (node (ref "H3") (pin "P5") (pinfunction "P5_P5") (pintype "bidirectional"))
      (node (ref "LED21") (pin "C") (pinfunction "C_C") (pintype "passive"))
      (node (ref "LED22") (pin "A") (pinfunction "A_A") (pintype "passive"))
      (node (ref "LED23") (pin "C") (pinfunction "C_C") (pintype "passive"))
      (node (ref "LED24") (pin "A") (pinfunction "A_A") (pintype "passive"))
      (node (ref "LED25") (pin "C") (pinfunction "C_C") (pintype "passive"))
      (node (ref "LED26") (pin "A") (pinfunction "A_A") (pintype "passive"))
      (node (ref "LED27") (pin "C") (pinfunction "C_C") (pintype "passive"))
      (node (ref "LED28") (pin "A") (pinfunction "A_A") (pintype "passive"))
      (node (ref "LED29") (pin "C") (pinfunction "C_C") (pintype "passive"))
      (node (ref "LED30") (pin "A") (pinfunction "A_A") (pintype "passive"))
    )
    (net (code "18") (name "Net-(H3-PadP6)") (class "Default")
      (node (ref "H3") (pin "P6") (pinfunction "P6_P6") (pintype "bidirectional"))
      (node (ref "LED139") (pin "A") (pinfunction "A_A") (pintype "passive"))
      (node (ref "LED140") (pin "C") (pinfunction "C_C") (pintype "passive"))
      (node (ref "LED19") (pin "A") (pinfunction "A_A") (pintype "passive"))
      (node (ref "LED20") (pin "C") (pinfunction "C_C") (pintype "passive"))
      (node (ref "LED80") (pin "C") (pinfunction "C_C") (pintype "passive"))
      (node (ref "LED81") (pin "A") (pinfunction "A_A") (pintype "passive"))
    )
    (net (code "19") (name "Net-(H4-PadP1)") (class "Default")
      (node (ref "H4") (pin "P1") (pinfunction "P1_P1") (pintype "bidirectional"))
      (node (ref "LED151") (pin "A") (pinfunction "A_A") (pintype "passive"))
      (node (ref "LED152") (pin "C") (pinfunction "C_C") (pintype "passive"))
      (node (ref "LED31") (pin "A") (pinfunction "A_A") (pintype "passive"))
      (node (ref "LED32") (pin "C") (pinfunction "C_C") (pintype "passive"))
      (node (ref "LED92") (pin "C") (pinfunction "C_C") (pintype "passive"))
      (node (ref "LED93") (pin "A") (pinfunction "A_A") (pintype "passive"))
    )
    (net (code "20") (name "Net-(H4-PadP2)") (class "Default")
      (node (ref "H4") (pin "P2") (pinfunction "P2_P2") (pintype "bidirectional"))
      (node (ref "LED153") (pin "A") (pinfunction "A_A") (pintype "passive"))
      (node (ref "LED154") (pin "C") (pinfunction "C_C") (pintype "passive"))
      (node (ref "LED33") (pin "A") (pinfunction "A_A") (pintype "passive"))
      (node (ref "LED34") (pin "C") (pinfunction "C_C") (pintype "passive"))
      (node (ref "LED94") (pin "C") (pinfunction "C_C") (pintype "passive"))
      (node (ref "LED95") (pin "A") (pinfunction "A_A") (pintype "passive"))
    )
    (net (code "21") (name "Net-(H4-PadP3)") (class "Default")
      (node (ref "H4") (pin "P3") (pinfunction "P3_P3") (pintype "bidirectional"))
      (node (ref "LED155") (pin "A") (pinfunction "A_A") (pintype "passive"))
      (node (ref "LED156") (pin "C") (pinfunction "C_C") (pintype "passive"))
      (node (ref "LED35") (pin "A") (pinfunction "A_A") (pintype "passive"))
      (node (ref "LED36") (pin "C") (pinfunction "C_C") (pintype "passive"))
      (node (ref "LED96") (pin "C") (pinfunction "C_C") (pintype "passive"))
      (node (ref "LED97") (pin "A") (pinfunction "A_A") (pintype "passive"))
    )
    (net (code "22") (name "Net-(H4-PadP4)") (class "Default")
      (node (ref "H4") (pin "P4") (pinfunction "P4_P4") (pintype "bidirectional"))
      (node (ref "LED147") (pin "A") (pinfunction "A_A") (pintype "passive"))
      (node (ref "LED148") (pin "C") (pinfunction "C_C") (pintype "passive"))
      (node (ref "LED27") (pin "A") (pinfunction "A_A") (pintype "passive"))
      (node (ref "LED28") (pin "C") (pinfunction "C_C") (pintype "passive"))
      (node (ref "LED88") (pin "C") (pinfunction "C_C") (pintype "passive"))
      (node (ref "LED89") (pin "A") (pinfunction "A_A") (pintype "passive"))
    )
    (net (code "23") (name "Net-(H4-PadP5)") (class "Default")
      (node (ref "H4") (pin "P5") (pinfunction "P5_P5") (pintype "bidirectional"))
      (node (ref "LED31") (pin "C") (pinfunction "C_C") (pintype "passive"))
      (node (ref "LED32") (pin "A") (pinfunction "A_A") (pintype "passive"))
      (node (ref "LED33") (pin "C") (pinfunction "C_C") (pintype "passive"))
      (node (ref "LED34") (pin "A") (pinfunction "A_A") (pintype "passive"))
      (node (ref "LED35") (pin "C") (pinfunction "C_C") (pintype "passive"))
      (node (ref "LED36") (pin "A") (pinfunction "A_A") (pintype "passive"))
      (node (ref "LED37") (pin "C") (pinfunction "C_C") (pintype "passive"))
      (node (ref "LED38") (pin "A") (pinfunction "A_A") (pintype "passive"))
      (node (ref "LED39") (pin "C") (pinfunction "C_C") (pintype "passive"))
      (node (ref "LED40") (pin "A") (pinfunction "A_A") (pintype "passive"))
    )
    (net (code "24") (name "Net-(H4-PadP6)") (class "Default")
      (node (ref "H4") (pin "P6") (pinfunction "P6_P6") (pintype "bidirectional"))
      (node (ref "LED149") (pin "A") (pinfunction "A_A") (pintype "passive"))
      (node (ref "LED150") (pin "C") (pinfunction "C_C") (pintype "passive"))
      (node (ref "LED29") (pin "A") (pinfunction "A_A") (pintype "passive"))
      (node (ref "LED30") (pin "C") (pinfunction "C_C") (pintype "passive"))
      (node (ref "LED90") (pin "C") (pinfunction "C_C") (pintype "passive"))
      (node (ref "LED91") (pin "A") (pinfunction "A_A") (pintype "passive"))
    )
    (net (code "25") (name "Net-(H5-PadP1)") (class "Default")
      (node (ref "H5") (pin "P1") (pinfunction "P1_P1") (pintype "bidirectional"))
      (node (ref "LED102") (pin "C") (pinfunction "C_C") (pintype "passive"))
      (node (ref "LED103") (pin "A") (pinfunction "A_A") (pintype "passive"))
      (node (ref "LED161") (pin "A") (pinfunction "A_A") (pintype "passive"))
      (node (ref "LED162") (pin "C") (pinfunction "C_C") (pintype "passive"))
      (node (ref "LED41") (pin "A") (pinfunction "A_A") (pintype "passive"))
      (node (ref "LED42") (pin "C") (pinfunction "C_C") (pintype "passive"))
    )
    (net (code "26") (name "Net-(H5-PadP2)") (class "Default")
      (node (ref "H5") (pin "P2") (pinfunction "P2_P2") (pintype "bidirectional"))
      (node (ref "LED104") (pin "C") (pinfunction "C_C") (pintype "passive"))
      (node (ref "LED105") (pin "A") (pinfunction "A_A") (pintype "passive"))
      (node (ref "LED163") (pin "A") (pinfunction "A_A") (pintype "passive"))
      (node (ref "LED164") (pin "C") (pinfunction "C_C") (pintype "passive"))
      (node (ref "LED43") (pin "A") (pinfunction "A_A") (pintype "passive"))
      (node (ref "LED44") (pin "C") (pinfunction "C_C") (pintype "passive"))
    )
    (net (code "27") (name "Net-(H5-PadP3)") (class "Default")
      (node (ref "H5") (pin "P3") (pinfunction "P3_P3") (pintype "bidirectional"))
      (node (ref "LED106") (pin "C") (pinfunction "C_C") (pintype "passive"))
      (node (ref "LED107") (pin "A") (pinfunction "A_A") (pintype "passive"))
      (node (ref "LED165") (pin "A") (pinfunction "A_A") (pintype "passive"))
      (node (ref "LED166") (pin "C") (pinfunction "C_C") (pintype "passive"))
      (node (ref "LED45") (pin "A") (pinfunction "A_A") (pintype "passive"))
      (node (ref "LED46") (pin "C") (pinfunction "C_C") (pintype "passive"))
    )
    (net (code "28") (name "Net-(H5-PadP4)") (class "Default")
      (node (ref "H5") (pin "P4") (pinfunction "P4_P4") (pintype "bidirectional"))
      (node (ref "LED157") (pin "A") (pinfunction "A_A") (pintype "passive"))
      (node (ref "LED158") (pin "C") (pinfunction "C_C") (pintype "passive"))
      (node (ref "LED37") (pin "A") (pinfunction "A_A") (pintype "passive"))
      (node (ref "LED38") (pin "C") (pinfunction "C_C") (pintype "passive"))
      (node (ref "LED98") (pin "C") (pinfunction "C_C") (pintype "passive"))
      (node (ref "LED99") (pin "A") (pinfunction "A_A") (pintype "passive"))
    )
    (net (code "29") (name "Net-(H5-PadP5)") (class "Default")
      (node (ref "H5") (pin "P5") (pinfunction "P5_P5") (pintype "bidirectional"))
      (node (ref "LED41") (pin "C") (pinfunction "C_C") (pintype "passive"))
      (node (ref "LED42") (pin "A") (pinfunction "A_A") (pintype "passive"))
      (node (ref "LED43") (pin "C") (pinfunction "C_C") (pintype "passive"))
      (node (ref "LED44") (pin "A") (pinfunction "A_A") (pintype "passive"))
      (node (ref "LED45") (pin "C") (pinfunction "C_C") (pintype "passive"))
      (node (ref "LED46") (pin "A") (pinfunction "A_A") (pintype "passive"))
      (node (ref "LED47") (pin "C") (pinfunction "C_C") (pintype "passive"))
      (node (ref "LED48") (pin "A") (pinfunction "A_A") (pintype "passive"))
      (node (ref "LED49") (pin "C") (pinfunction "C_C") (pintype "passive"))
      (node (ref "LED50") (pin "A") (pinfunction "A_A") (pintype "passive"))
    )
    (net (code "30") (name "Net-(H5-PadP6)") (class "Default")
      (node (ref "H5") (pin "P6") (pinfunction "P6_P6") (pintype "bidirectional"))
      (node (ref "LED100") (pin "C") (pinfunction "C_C") (pintype "passive"))
      (node (ref "LED101") (pin "A") (pinfunction "A_A") (pintype "passive"))
      (node (ref "LED159") (pin "A") (pinfunction "A_A") (pintype "passive"))
      (node (ref "LED160") (pin "C") (pinfunction "C_C") (pintype "passive"))
      (node (ref "LED39") (pin "A") (pinfunction "A_A") (pintype "passive"))
      (node (ref "LED40") (pin "C") (pinfunction "C_C") (pintype "passive"))
    )
    (net (code "31") (name "Net-(H6-PadP1)") (class "Default")
      (node (ref "H6") (pin "P1") (pinfunction "P1_P1") (pintype "bidirectional"))
      (node (ref "LED112") (pin "C") (pinfunction "C_C") (pintype "passive"))
      (node (ref "LED113") (pin "A") (pinfunction "A_A") (pintype "passive"))
      (node (ref "LED171") (pin "A") (pinfunction "A_A") (pintype "passive"))
      (node (ref "LED172") (pin "C") (pinfunction "C_C") (pintype "passive"))
      (node (ref "LED51") (pin "A") (pinfunction "A_A") (pintype "passive"))
      (node (ref "LED52") (pin "C") (pinfunction "C_C") (pintype "passive"))
    )
    (net (code "32") (name "Net-(H6-PadP2)") (class "Default")
      (node (ref "H6") (pin "P2") (pinfunction "P2_P2") (pintype "bidirectional"))
      (node (ref "LED114") (pin "C") (pinfunction "C_C") (pintype "passive"))
      (node (ref "LED115") (pin "A") (pinfunction "A_A") (pintype "passive"))
      (node (ref "LED173") (pin "A") (pinfunction "A_A") (pintype "passive"))
      (node (ref "LED174") (pin "C") (pinfunction "C_C") (pintype "passive"))
      (node (ref "LED53") (pin "A") (pinfunction "A_A") (pintype "passive"))
      (node (ref "LED54") (pin "C") (pinfunction "C_C") (pintype "passive"))
    )
    (net (code "33") (name "Net-(H6-PadP3)") (class "Default")
      (node (ref "H6") (pin "P3") (pinfunction "P3_P3") (pintype "bidirectional"))
      (node (ref "LED116") (pin "C") (pinfunction "C_C") (pintype "passive"))
      (node (ref "LED117") (pin "A") (pinfunction "A_A") (pintype "passive"))
      (node (ref "LED175") (pin "A") (pinfunction "A_A") (pintype "passive"))
      (node (ref "LED176") (pin "C") (pinfunction "C_C") (pintype "passive"))
      (node (ref "LED55") (pin "A") (pinfunction "A_A") (pintype "passive"))
      (node (ref "LED56") (pin "C") (pinfunction "C_C") (pintype "passive"))
    )
    (net (code "34") (name "Net-(H6-PadP4)") (class "Default")
      (node (ref "H6") (pin "P4") (pinfunction "P4_P4") (pintype "bidirectional"))
      (node (ref "LED108") (pin "C") (pinfunction "C_C") (pintype "passive"))
      (node (ref "LED109") (pin "A") (pinfunction "A_A") (pintype "passive"))
      (node (ref "LED167") (pin "A") (pinfunction "A_A") (pintype "passive"))
      (node (ref "LED168") (pin "C") (pinfunction "C_C") (pintype "passive"))
      (node (ref "LED47") (pin "A") (pinfunction "A_A") (pintype "passive"))
      (node (ref "LED48") (pin "C") (pinfunction "C_C") (pintype "passive"))
    )
    (net (code "35") (name "Net-(H6-PadP5)") (class "Default")
      (node (ref "H6") (pin "P5") (pinfunction "P5_P5") (pintype "bidirectional"))
      (node (ref "LED51") (pin "C") (pinfunction "C_C") (pintype "passive"))
      (node (ref "LED52") (pin "A") (pinfunction "A_A") (pintype "passive"))
      (node (ref "LED53") (pin "C") (pinfunction "C_C") (pintype "passive"))
      (node (ref "LED54") (pin "A") (pinfunction "A_A") (pintype "passive"))
      (node (ref "LED55") (pin "C") (pinfunction "C_C") (pintype "passive"))
      (node (ref "LED56") (pin "A") (pinfunction "A_A") (pintype "passive"))
      (node (ref "LED57") (pin "C") (pinfunction "C_C") (pintype "passive"))
      (node (ref "LED58") (pin "A") (pinfunction "A_A") (pintype "passive"))
      (node (ref "LED59") (pin "C") (pinfunction "C_C") (pintype "passive"))
      (node (ref "LED60") (pin "A") (pinfunction "A_A") (pintype "passive"))
    )
    (net (code "36") (name "Net-(H6-PadP6)") (class "Default")
      (node (ref "H6") (pin "P6") (pinfunction "P6_P6") (pintype "bidirectional"))
      (node (ref "LED110") (pin "C") (pinfunction "C_C") (pintype "passive"))
      (node (ref "LED111") (pin "A") (pinfunction "A_A") (pintype "passive"))
      (node (ref "LED169") (pin "A") (pinfunction "A_A") (pintype "passive"))
      (node (ref "LED170") (pin "C") (pinfunction "C_C") (pintype "passive"))
      (node (ref "LED49") (pin "A") (pinfunction "A_A") (pintype "passive"))
      (node (ref "LED50") (pin "C") (pinfunction "C_C") (pintype "passive"))
    )
    (net (code "37") (name "Net-(H7-PadP1)") (class "Default")
      (node (ref "H7") (pin "P1") (pinfunction "P1_P1") (pintype "bidirectional"))
      (node (ref "LED62") (pin "A") (pinfunction "A_A") (pintype "passive"))
      (node (ref "LED63") (pin "C") (pinfunction "C_C") (pintype "passive"))
      (node (ref "LED64") (pin "A") (pinfunction "A_A") (pintype "passive"))
      (node (ref "LED65") (pin "C") (pinfunction "C_C") (pintype "passive"))
      (node (ref "LED66") (pin "A") (pinfunction "A_A") (pintype "passive"))
      (node (ref "LED67") (pin "C") (pinfunction "C_C") (pintype "passive"))
      (node (ref "LED68") (pin "A") (pinfunction "A_A") (pintype "passive"))
      (node (ref "LED69") (pin "C") (pinfunction "C_C") (pintype "passive"))
      (node (ref "LED70") (pin "A") (pinfunction "A_A") (pintype "passive"))
      (node (ref "LED71") (pin "C") (pinfunction "C_C") (pintype "passive"))
    )
    (net (code "38") (name "Net-(H7-PadP2)") (class "Default")
      (node (ref "H7") (pin "P2") (pinfunction "P2_P2") (pintype "bidirectional"))
      (node (ref "LED171") (pin "C") (pinfunction "C_C") (pintype "passive"))
      (node (ref "LED172") (pin "A") (pinfunction "A_A") (pintype "passive"))
      (node (ref "LED173") (pin "C") (pinfunction "C_C") (pintype "passive"))
      (node (ref "LED174") (pin "A") (pinfunction "A_A") (pintype "passive"))
      (node (ref "LED175") (pin "C") (pinfunction "C_C") (pintype "passive"))
      (node (ref "LED176") (pin "A") (pinfunction "A_A") (pintype "passive"))
      (node (ref "LED177") (pin "C") (pinfunction "C_C") (pintype "passive"))
      (node (ref "LED178") (pin "A") (pinfunction "A_A") (pintype "passive"))
      (node (ref "LED179") (pin "C") (pinfunction "C_C") (pintype "passive"))
      (node (ref "LED180") (pin "A") (pinfunction "A_A") (pintype "passive"))
    )
    (net (code "39") (name "Net-(H7-PadP3)") (class "Default")
      (node (ref "H7") (pin "P3") (pinfunction "P3_P3") (pintype "bidirectional"))
      (node (ref "LED72") (pin "A") (pinfunction "A_A") (pintype "passive"))
      (node (ref "LED73") (pin "C") (pinfunction "C_C") (pintype "passive"))
      (node (ref "LED74") (pin "A") (pinfunction "A_A") (pintype "passive"))
      (node (ref "LED75") (pin "C") (pinfunction "C_C") (pintype "passive"))
      (node (ref "LED76") (pin "A") (pinfunction "A_A") (pintype "passive"))
      (node (ref "LED77") (pin "C") (pinfunction "C_C") (pintype "passive"))
      (node (ref "LED78") (pin "A") (pinfunction "A_A") (pintype "passive"))
      (node (ref "LED79") (pin "C") (pinfunction "C_C") (pintype "passive"))
      (node (ref "LED80") (pin "A") (pinfunction "A_A") (pintype "passive"))
      (node (ref "LED81") (pin "C") (pinfunction "C_C") (pintype "passive"))
    )
    (net (code "40") (name "Net-(H7-PadP4)") (class "Default")
      (node (ref "H7") (pin "P4") (pinfunction "P4_P4") (pintype "bidirectional"))
      (node (ref "LED121") (pin "C") (pinfunction "C_C") (pintype "passive"))
      (node (ref "LED122") (pin "A") (pinfunction "A_A") (pintype "passive"))
      (node (ref "LED123") (pin "C") (pinfunction "C_C") (pintype "passive"))
      (node (ref "LED124") (pin "A") (pinfunction "A_A") (pintype "passive"))
      (node (ref "LED125") (pin "C") (pinfunction "C_C") (pintype "passive"))
      (node (ref "LED126") (pin "A") (pinfunction "A_A") (pintype "passive"))
      (node (ref "LED127") (pin "C") (pinfunction "C_C") (pintype "passive"))
      (node (ref "LED128") (pin "A") (pinfunction "A_A") (pintype "passive"))
      (node (ref "LED129") (pin "C") (pinfunction "C_C") (pintype "passive"))
      (node (ref "LED130") (pin "A") (pinfunction "A_A") (pintype "passive"))
    )
    (net (code "41") (name "Net-(H8-PadP1)") (class "Default")
      (node (ref "H8") (pin "P1") (pinfunction "P1_P1") (pintype "bidirectional"))
      (node (ref "LED82") (pin "A") (pinfunction "A_A") (pintype "passive"))
      (node (ref "LED83") (pin "C") (pinfunction "C_C") (pintype "passive"))
      (node (ref "LED84") (pin "A") (pinfunction "A_A") (pintype "passive"))
      (node (ref "LED85") (pin "C") (pinfunction "C_C") (pintype "passive"))
      (node (ref "LED86") (pin "A") (pinfunction "A_A") (pintype "passive"))
      (node (ref "LED87") (pin "C") (pinfunction "C_C") (pintype "passive"))
      (node (ref "LED88") (pin "A") (pinfunction "A_A") (pintype "passive"))
      (node (ref "LED89") (pin "C") (pinfunction "C_C") (pintype "passive"))
      (node (ref "LED90") (pin "A") (pinfunction "A_A") (pintype "passive"))
      (node (ref "LED91") (pin "C") (pinfunction "C_C") (pintype "passive"))
    )
    (net (code "42") (name "Net-(H8-PadP2)") (class "Default")
      (node (ref "H8") (pin "P2") (pinfunction "P2_P2") (pintype "bidirectional"))
      (node (ref "LED131") (pin "C") (pinfunction "C_C") (pintype "passive"))
      (node (ref "LED132") (pin "A") (pinfunction "A_A") (pintype "passive"))
      (node (ref "LED133") (pin "C") (pinfunction "C_C") (pintype "passive"))
      (node (ref "LED134") (pin "A") (pinfunction "A_A") (pintype "passive"))
      (node (ref "LED135") (pin "C") (pinfunction "C_C") (pintype "passive"))
      (node (ref "LED136") (pin "A") (pinfunction "A_A") (pintype "passive"))
      (node (ref "LED137") (pin "C") (pinfunction "C_C") (pintype "passive"))
      (node (ref "LED138") (pin "A") (pinfunction "A_A") (pintype "passive"))
      (node (ref "LED139") (pin "C") (pinfunction "C_C") (pintype "passive"))
      (node (ref "LED140") (pin "A") (pinfunction "A_A") (pintype "passive"))
    )
    (net (code "43") (name "Net-(H8-PadP3)") (class "Default")
      (node (ref "H8") (pin "P3") (pinfunction "P3_P3") (pintype "bidirectional"))
      (node (ref "LED100") (pin "A") (pinfunction "A_A") (pintype "passive"))
      (node (ref "LED101") (pin "C") (pinfunction "C_C") (pintype "passive"))
      (node (ref "LED92") (pin "A") (pinfunction "A_A") (pintype "passive"))
      (node (ref "LED93") (pin "C") (pinfunction "C_C") (pintype "passive"))
      (node (ref "LED94") (pin "A") (pinfunction "A_A") (pintype "passive"))
      (node (ref "LED95") (pin "C") (pinfunction "C_C") (pintype "passive"))
      (node (ref "LED96") (pin "A") (pinfunction "A_A") (pintype "passive"))
      (node (ref "LED97") (pin "C") (pinfunction "C_C") (pintype "passive"))
      (node (ref "LED98") (pin "A") (pinfunction "A_A") (pintype "passive"))
      (node (ref "LED99") (pin "C") (pinfunction "C_C") (pintype "passive"))
    )
    (net (code "44") (name "Net-(H8-PadP4)") (class "Default")
      (node (ref "H8") (pin "P4") (pinfunction "P4_P4") (pintype "bidirectional"))
      (node (ref "LED141") (pin "C") (pinfunction "C_C") (pintype "passive"))
      (node (ref "LED142") (pin "A") (pinfunction "A_A") (pintype "passive"))
      (node (ref "LED143") (pin "C") (pinfunction "C_C") (pintype "passive"))
      (node (ref "LED144") (pin "A") (pinfunction "A_A") (pintype "passive"))
      (node (ref "LED145") (pin "C") (pinfunction "C_C") (pintype "passive"))
      (node (ref "LED146") (pin "A") (pinfunction "A_A") (pintype "passive"))
      (node (ref "LED147") (pin "C") (pinfunction "C_C") (pintype "passive"))
      (node (ref "LED148") (pin "A") (pinfunction "A_A") (pintype "passive"))
      (node (ref "LED149") (pin "C") (pinfunction "C_C") (pintype "passive"))
      (node (ref "LED150") (pin "A") (pinfunction "A_A") (pintype "passive"))
    )
    (net (code "45") (name "Net-(H9-PadP1)") (class "Default")
      (node (ref "H9") (pin "P1") (pinfunction "P1_P1") (pintype "bidirectional"))
      (node (ref "LED102") (pin "A") (pinfunction "A_A") (pintype "passive"))
      (node (ref "LED103") (pin "C") (pinfunction "C_C") (pintype "passive"))
      (node (ref "LED104") (pin "A") (pinfunction "A_A") (pintype "passive"))
      (node (ref "LED105") (pin "C") (pinfunction "C_C") (pintype "passive"))
      (node (ref "LED106") (pin "A") (pinfunction "A_A") (pintype "passive"))
      (node (ref "LED107") (pin "C") (pinfunction "C_C") (pintype "passive"))
      (node (ref "LED108") (pin "A") (pinfunction "A_A") (pintype "passive"))
      (node (ref "LED109") (pin "C") (pinfunction "C_C") (pintype "passive"))
      (node (ref "LED110") (pin "A") (pinfunction "A_A") (pintype "passive"))
      (node (ref "LED111") (pin "C") (pinfunction "C_C") (pintype "passive"))
    )
    (net (code "46") (name "Net-(H9-PadP2)") (class "Default")
      (node (ref "H9") (pin "P2") (pinfunction "P2_P2") (pintype "bidirectional"))
      (node (ref "LED151") (pin "C") (pinfunction "C_C") (pintype "passive"))
      (node (ref "LED152") (pin "A") (pinfunction "A_A") (pintype "passive"))
      (node (ref "LED153") (pin "C") (pinfunction "C_C") (pintype "passive"))
      (node (ref "LED154") (pin "A") (pinfunction "A_A") (pintype "passive"))
      (node (ref "LED155") (pin "C") (pinfunction "C_C") (pintype "passive"))
      (node (ref "LED156") (pin "A") (pinfunction "A_A") (pintype "passive"))
      (node (ref "LED157") (pin "C") (pinfunction "C_C") (pintype "passive"))
      (node (ref "LED158") (pin "A") (pinfunction "A_A") (pintype "passive"))
      (node (ref "LED159") (pin "C") (pinfunction "C_C") (pintype "passive"))
      (node (ref "LED160") (pin "A") (pinfunction "A_A") (pintype "passive"))
    )
    (net (code "47") (name "Net-(H9-PadP3)") (class "Default")
      (node (ref "H9") (pin "P3") (pinfunction "P3_P3") (pintype "bidirectional"))
      (node (ref "LED112") (pin "A") (pinfunction "A_A") (pintype "passive"))
      (node (ref "LED113") (pin "C") (pinfunction "C_C") (pintype "passive"))
      (node (ref "LED114") (pin "A") (pinfunction "A_A") (pintype "passive"))
      (node (ref "LED115") (pin "C") (pinfunction "C_C") (pintype "passive"))
      (node (ref "LED116") (pin "A") (pinfunction "A_A") (pintype "passive"))
      (node (ref "LED117") (pin "C") (pinfunction "C_C") (pintype "passive"))
      (node (ref "LED118") (pin "A") (pinfunction "A_A") (pintype "passive"))
      (node (ref "LED119") (pin "C") (pinfunction "C_C") (pintype "passive"))
      (node (ref "LED120") (pin "A") (pinfunction "A_A") (pintype "passive"))
      (node (ref "LED61") (pin "C") (pinfunction "C_C") (pintype "passive"))
    )
    (net (code "48") (name "Net-(H9-PadP4)") (class "Default")
      (node (ref "H9") (pin "P4") (pinfunction "P4_P4") (pintype "bidirectional"))
      (node (ref "LED161") (pin "C") (pinfunction "C_C") (pintype "passive"))
      (node (ref "LED162") (pin "A") (pinfunction "A_A") (pintype "passive"))
      (node (ref "LED163") (pin "C") (pinfunction "C_C") (pintype "passive"))
      (node (ref "LED164") (pin "A") (pinfunction "A_A") (pintype "passive"))
      (node (ref "LED165") (pin "C") (pinfunction "C_C") (pintype "passive"))
      (node (ref "LED166") (pin "A") (pinfunction "A_A") (pintype "passive"))
      (node (ref "LED167") (pin "C") (pinfunction "C_C") (pintype "passive"))
      (node (ref "LED168") (pin "A") (pinfunction "A_A") (pintype "passive"))
      (node (ref "LED169") (pin "C") (pinfunction "C_C") (pintype "passive"))
      (node (ref "LED170") (pin "A") (pinfunction "A_A") (pintype "passive"))
    )
  )
)
